# imu_cpu.net
KiCad netlist of a schematic drawn in Altium Designer
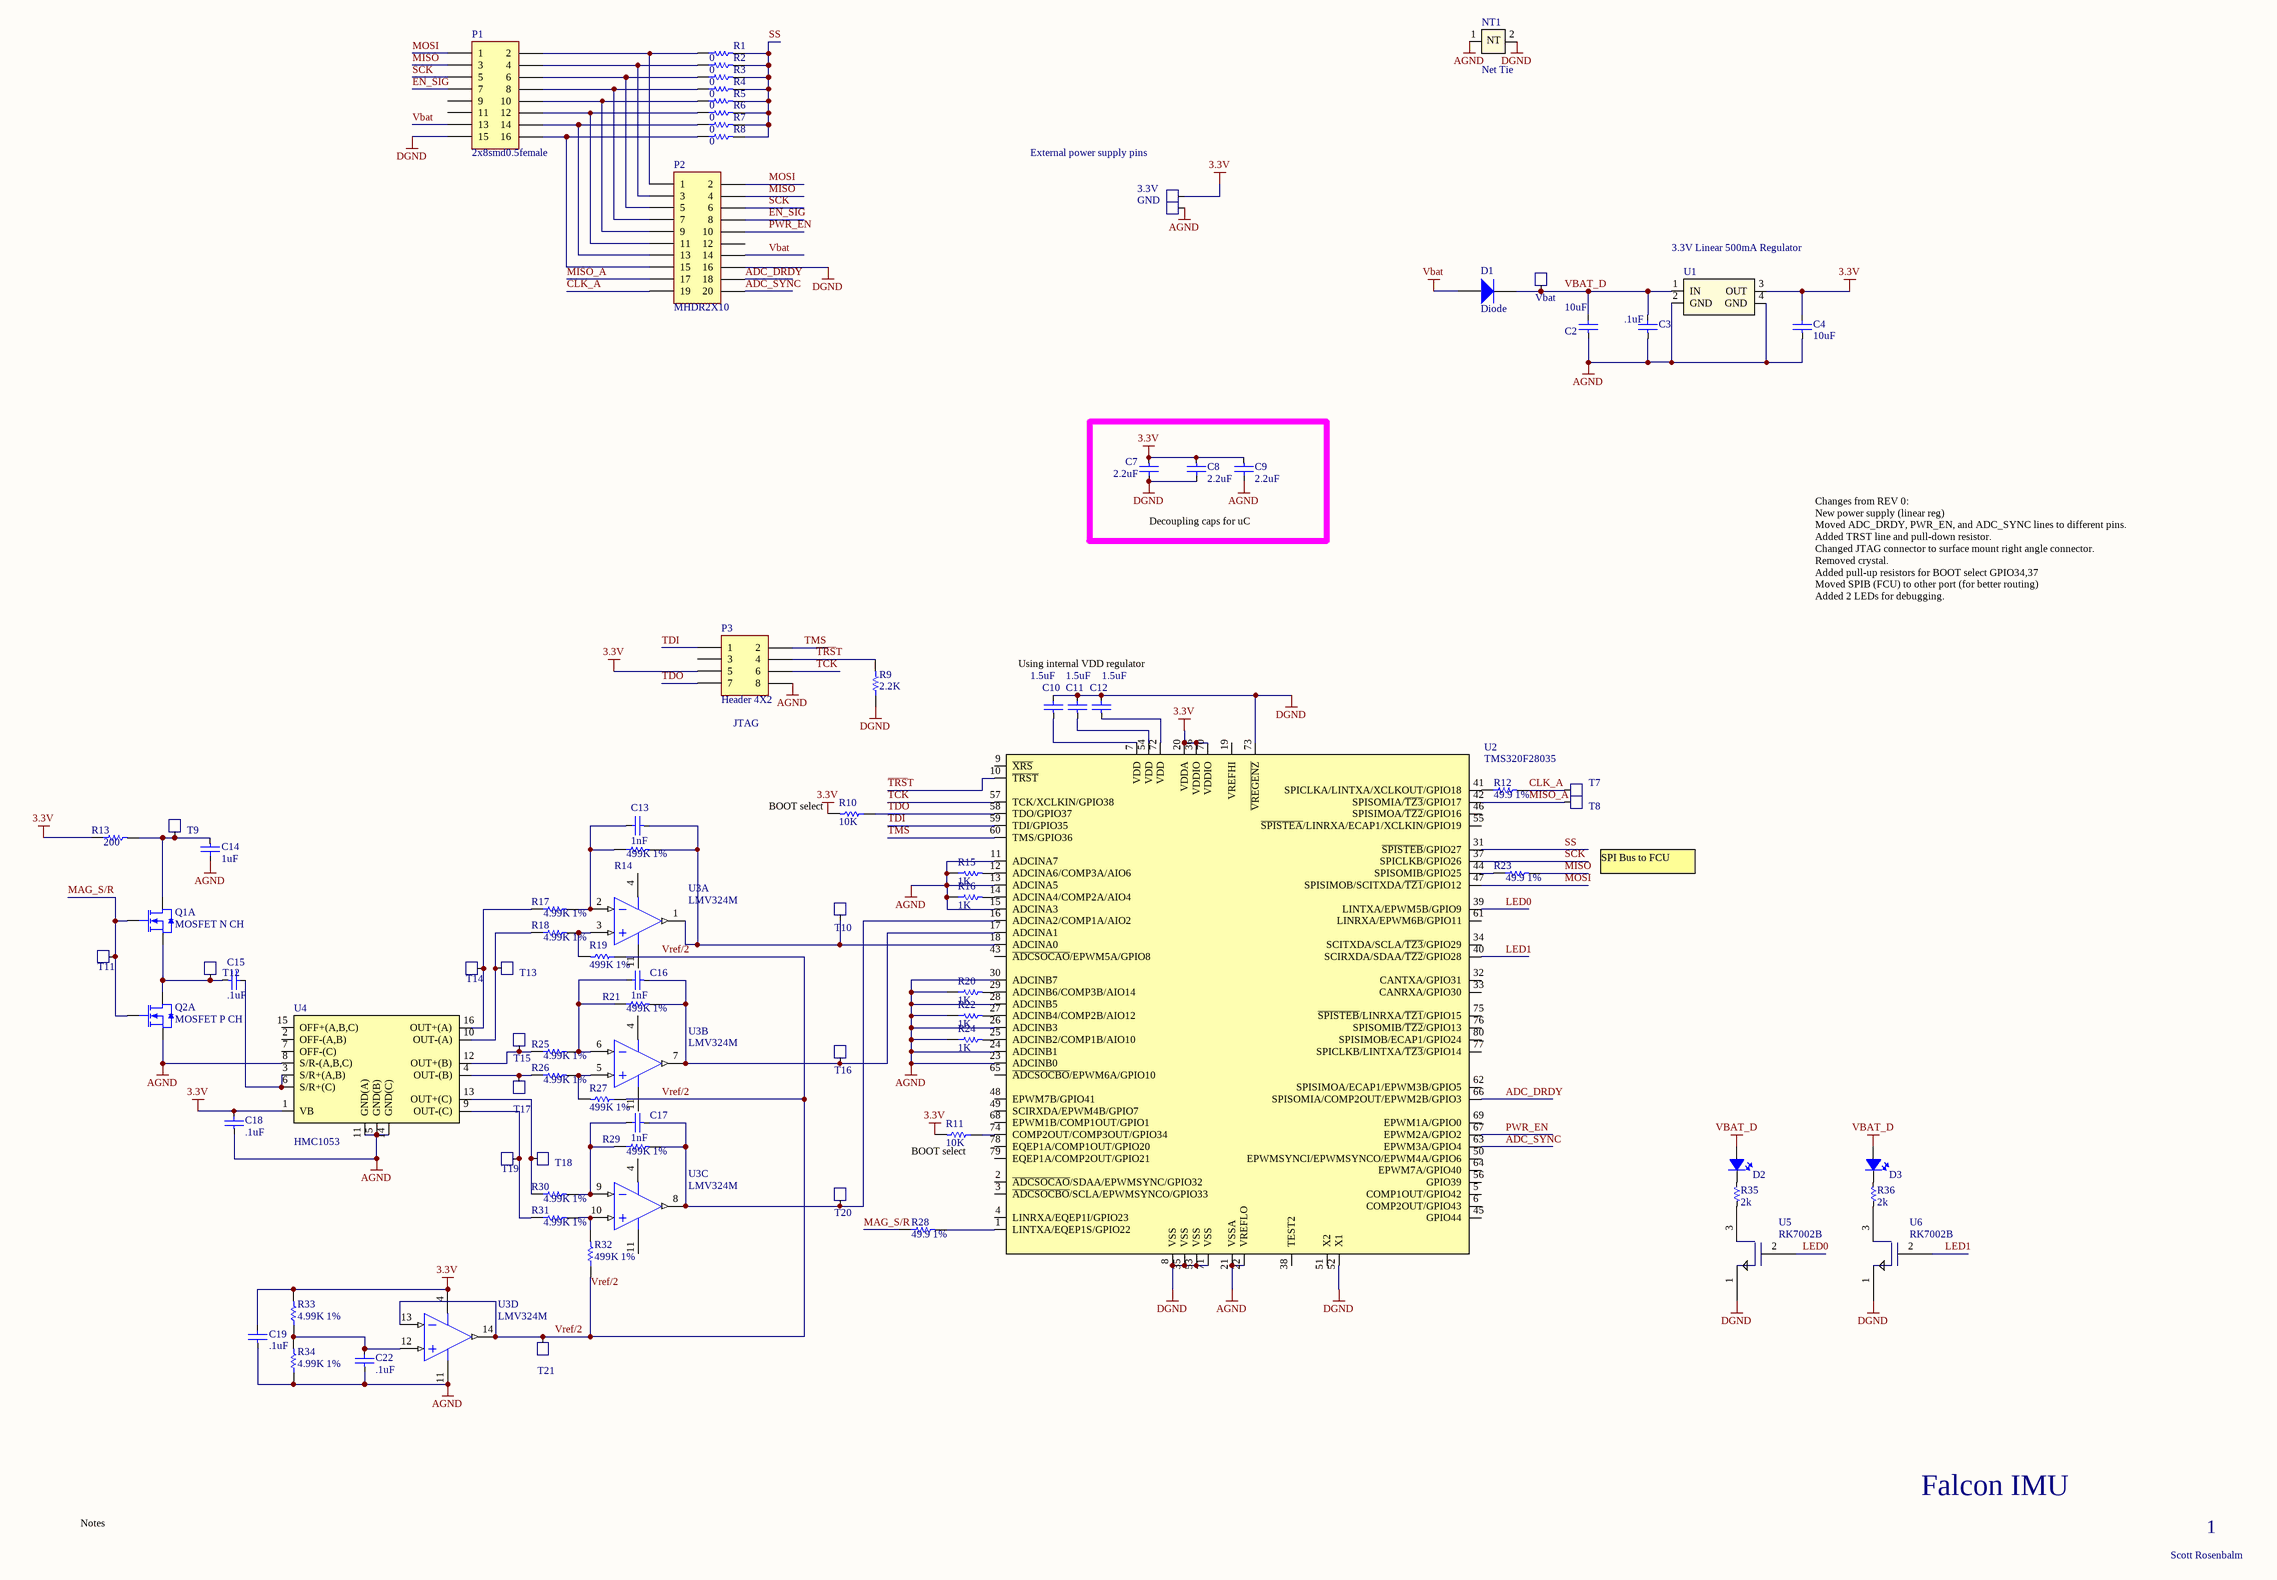
[diagram p0: imu_cpu.SchDoc]

(export (version "E")
  (design (tool "Eeschema 10.0.6"))
  (components
    (comp (ref "3.3V") (value "TEST_PAD") (footprint "TEST_PAD") (libsource (lib "") (part "TEST_PAD_1")))
    (comp (ref "C2")
      (value "10uF")
      (footprint "1210 (3225)")
      (fields (field (name "PART NO.") "810-C3225X7R1E106M"))
      (libsource (lib "SMT Chip") (part "Capacitor"))
    )
    (comp (ref "C3")
      (value ".1uF")
      (footprint "0603 (1608)")
      (fields (field (name "MANUFACTURER") "Murata") (field (name "PART NO.") "490-1524-1-ND"))
      (libsource (lib "SMT Chip") (part "Capacitor"))
    )
    (comp (ref "C4")
      (value "10uF")
      (footprint "1206 (3216)")
      (fields (field (name "PART NO.") "810-C3216X5R1A106M"))
      (libsource (lib "SMT Chip") (part "Capacitor"))
    )
    (comp (ref "C7")
      (value "2.2uF")
      (footprint "0603 (1608)")
      (fields
        (field (name "MANUFACTURER") "TDK")
        (field (name "PART NO.") "445-5167-1-ND")
        (field (name "TOLERANCE") "20%")
      )
      (libsource (lib "SMT Chip") (part "Capacitor"))
    )
    (comp (ref "C8")
      (value "2.2uF")
      (footprint "0603 (1608)")
      (fields
        (field (name "MANUFACTURER") "TDK")
        (field (name "PART NO.") "445-5167-1-ND")
        (field (name "TOLERANCE") "20%")
      )
      (libsource (lib "SMT Chip") (part "Capacitor"))
    )
    (comp (ref "C9")
      (value "2.2uF")
      (footprint "0603 (1608)")
      (fields
        (field (name "MANUFACTURER") "TDK")
        (field (name "PART NO.") "445-5167-1-ND")
        (field (name "TOLERANCE") "20%")
      )
      (libsource (lib "SMT Chip") (part "Capacitor"))
    )
    (comp (ref "C10")
      (value "1.5uF")
      (footprint "0805 (2012)")
      (fields (field (name "MANUFACTURER") "Murata") (field (name "PART NO.") "490-1740-1-ND"))
      (libsource (lib "SMT Chip") (part "Capacitor"))
    )
    (comp (ref "C11")
      (value "1.5uF")
      (footprint "0805 (2012)")
      (fields (field (name "MANUFACTURER") "Murata") (field (name "PART NO.") "490-1740-1-ND"))
      (libsource (lib "SMT Chip") (part "Capacitor"))
    )
    (comp (ref "C12")
      (value "1.5uF")
      (footprint "0805 (2012)")
      (fields (field (name "MANUFACTURER") "Murata") (field (name "PART NO.") "490-1740-1-ND"))
      (libsource (lib "SMT Chip") (part "Capacitor"))
    )
    (comp (ref "C13")
      (value "1nF")
      (footprint "0603 (1608)")
      (fields
        (field (name "MANUFACTURER") "Murata")
        (field (name "PART NO.") "490-1451-1-ND")
        (field (name "TOLERANCE") "5%")
      )
      (libsource (lib "SMT Chip") (part "Capacitor"))
    )
    (comp (ref "C14")
      (value "1uF")
      (footprint "0603 (1608)")
      (fields
        (field (name "MANUFACTURER") "Murata")
        (field (name "PART NO.") "81-GRM188R61E105KA12")
        (field (name "TOLERANCE") "10%")
      )
      (libsource (lib "SMT Chip") (part "Capacitor"))
    )
    (comp (ref "C15")
      (value ".1uF")
      (footprint "0603 (1608)")
      (fields
        (field (name "MANUFACTURER") "Murata")
        (field (name "PART NO.") "490-1524-1-ND")
        (field (name "Comment") "Capacitor")
      )
      (libsource (lib "SMT Chip") (part "Capacitor"))
    )
    (comp (ref "C16")
      (value "1nF")
      (footprint "0603 (1608)")
      (fields
        (field (name "MANUFACTURER") "Murata")
        (field (name "PART NO.") "490-1451-1-ND")
        (field (name "TOLERANCE") "5%")
      )
      (libsource (lib "SMT Chip") (part "Capacitor"))
    )
    (comp (ref "C17")
      (value "1nF")
      (footprint "0603 (1608)")
      (fields
        (field (name "MANUFACTURER") "Murata")
        (field (name "PART NO.") "490-1451-1-ND")
        (field (name "TOLERANCE") "5%")
      )
      (libsource (lib "SMT Chip") (part "Capacitor"))
    )
    (comp (ref "C18")
      (value ".1uF")
      (footprint "0603 (1608)")
      (fields
        (field (name "MANUFACTURER") "Murata")
        (field (name "PART NO.") "490-1524-1-ND")
        (field (name "Comment") "Capacitor")
      )
      (libsource (lib "SMT Chip") (part "Capacitor"))
    )
    (comp (ref "C19")
      (value ".1uF")
      (footprint "0603 (1608)")
      (fields
        (field (name "MANUFACTURER") "Murata")
        (field (name "PART NO.") "490-1524-1-ND")
        (field (name "Comment") "Capacitor")
      )
      (libsource (lib "SMT Chip") (part "Capacitor"))
    )
    (comp (ref "C22")
      (value ".1uF")
      (footprint "0603 (1608)")
      (fields
        (field (name "MANUFACTURER") "Murata")
        (field (name "PART NO.") "490-1524-1-ND")
        (field (name "Comment") "Capacitor")
      )
      (libsource (lib "SMT Chip") (part "Capacitor"))
    )
    (comp (ref "D1")
      (value "Diode")
      (footprint "0603(1608) diode - line on pin2")
      (description "Reverse voltage protection diode")
      (fields (field (name "PART NO.") "641-1332-1-ND"))
      (libsource (lib "Miscellaneous Devices") (part "Diode"))
    )
    (comp (ref "D2")
      (value "LED")
      (footprint "LED 0603 (1608)")
      (fields (field (name "PART NO.") "LTST-C170XXX") (field (name "MANUFACTURER") "Lite-On"))
      (libsource (lib "Diode") (part "LED"))
    )
    (comp (ref "D3")
      (value "LED")
      (footprint "LED 0603 (1608)")
      (fields (field (name "PART NO.") "LTST-C170XXX") (field (name "MANUFACTURER") "Lite-On"))
      (libsource (lib "Diode") (part "LED"))
    )
    (comp (ref "GND") (value "TEST_PAD") (footprint "TEST_PAD") (libsource (lib "") (part "TEST_PAD_1")))
    (comp (ref "NT1") (value "Net Tie") (footprint "NET_TIE") (libsource (lib "imu") (part "NET_TIE")))
    (comp (ref "P1")
      (value "2x8smd0.5female")
      (footprint "Header, right hole")
      (fields (field (name "PART NO.") "S9007E-08-ND"))
      (libsource (lib "imu") (part "2x8smd0.5female"))
    )
    (comp (ref "P2")
      (value "MHDR2X10")
      (footprint "S9013E-10-ND")
      (description "Header, 10-Pin, Dual row, Male")
      (fields (field (name "PART NO.") "S9013E-10-ND"))
      (libsource (lib "Miscellaneous Connectors") (part "MHDR2X10"))
    )
    (comp (ref "P3")
      (value "Header 4X2")
      (footprint "right-angle female header 8-pin")
      (description "Header, 4-Pin, Dual row")
      (fields (field (name "PART NO.") "3M9279CT-ND"))
      (libsource (lib "Miscellaneous Connectors") (part "Header 4X2"))
    )
    (comp (ref "Q1")
      (value "MOSFET N CH")
      (footprint "SOT563F")
      (fields (field (name "PART NO.") "SI1035X-T1-E3CT-ND") (field (name "MANUFACTURER") "Vishay Siliconx"))
      (libsource (lib "imu") (part "MOSFETs"))
    )
    (comp (ref "Q2")
      (value "MOSFET P CH")
      (footprint "SOT563F")
      (fields (field (name "PART NO.") "SI1035X-T1-E3CT-ND") (field (name "MANUFACTURER") "Vishay Siliconx"))
      (libsource (lib "imu") (part "MOSFETs"))
    )
    (comp (ref "R1")
      (value "0")
      (footprint "0603 (1608)")
      (description "Resistor")
      (fields (field (name "PART NO.") "P0.0GCT-ND") (field (name "Comment") "SS Jumper"))
      (libsource (lib "Miscellaneous Devices") (part "Res1"))
    )
    (comp (ref "R2")
      (value "0")
      (footprint "0603 (1608)")
      (description "Resistor")
      (fields (field (name "PART NO.") "P0.0GCT-ND") (field (name "Comment") "SS Jumper"))
      (libsource (lib "Miscellaneous Devices") (part "Res1"))
    )
    (comp (ref "R3")
      (value "0")
      (footprint "0603 (1608)")
      (description "Resistor")
      (fields (field (name "PART NO.") "P0.0GCT-ND") (field (name "Comment") "SS Jumper"))
      (libsource (lib "Miscellaneous Devices") (part "Res1"))
    )
    (comp (ref "R4")
      (value "0")
      (footprint "0603 (1608)")
      (description "Resistor")
      (fields (field (name "PART NO.") "P0.0GCT-ND") (field (name "Comment") "SS Jumper"))
      (libsource (lib "Miscellaneous Devices") (part "Res1"))
    )
    (comp (ref "R5")
      (value "0")
      (footprint "0603 (1608)")
      (description "Resistor")
      (fields (field (name "PART NO.") "P0.0GCT-ND") (field (name "Comment") "SS Jumper"))
      (libsource (lib "Miscellaneous Devices") (part "Res1"))
    )
    (comp (ref "R6")
      (value "0")
      (footprint "0603 (1608)")
      (description "Resistor")
      (fields (field (name "PART NO.") "P0.0GCT-ND") (field (name "Comment") "SS Jumper"))
      (libsource (lib "Miscellaneous Devices") (part "Res1"))
    )
    (comp (ref "R7")
      (value "0")
      (footprint "0603 (1608)")
      (description "Resistor")
      (fields (field (name "PART NO.") "P0.0GCT-ND") (field (name "Comment") "SS Jumper"))
      (libsource (lib "Miscellaneous Devices") (part "Res1"))
    )
    (comp (ref "R8")
      (value "0")
      (footprint "0603 (1608)")
      (description "Resistor")
      (fields (field (name "PART NO.") "P0.0GCT-ND") (field (name "Comment") "SS Jumper"))
      (libsource (lib "Miscellaneous Devices") (part "Res1"))
    )
    (comp (ref "R9")
      (value "2.2K")
      (footprint "0603 (1608)")
      (description "Resistor")
      (fields (field (name "PART NO.") "P2.2KGCT-ND") (field (name "Comment") "Res1"))
      (libsource (lib "Miscellaneous Devices") (part "Res1"))
    )
    (comp (ref "R10")
      (value "10K")
      (footprint "0603 (1608)")
      (description "Resistor")
      (fields (field (name "PART NO.") "541-10KGCT-ND") (field (name "Comment") "Res1"))
      (libsource (lib "Miscellaneous Devices") (part "Res1"))
    )
    (comp (ref "R11")
      (value "10K")
      (footprint "0603 (1608)")
      (description "Resistor")
      (fields (field (name "PART NO.") "541-10KGCT-ND") (field (name "Comment") "Res1"))
      (libsource (lib "Miscellaneous Devices") (part "Res1"))
    )
    (comp (ref "R12")
      (value "49.9 1%")
      (footprint "0603 (1608)")
      (description "Resistor")
      (fields (field (name "PART NO.") "P49.9HCT-ND") (field (name "Comment") "931 1%"))
      (libsource (lib "Miscellaneous Devices") (part "Res1"))
    )
    (comp (ref "R13")
      (value "200")
      (footprint "0603 (1608)")
      (description "Resistor")
      (fields (field (name "PART NO.") "P200GCT-ND"))
      (libsource (lib "Miscellaneous Devices") (part "Res1"))
    )
    (comp (ref "R14")
      (value "499K 1%")
      (footprint "0603 (1608)")
      (description "Resistor")
      (fields (field (name "PART NO.") "P499KHCT-ND"))
      (libsource (lib "Miscellaneous Devices") (part "Res1"))
    )
    (comp (ref "R15")
      (value "1K")
      (footprint "0603 (1608)")
      (description "Resistor")
      (fields (field (name "PART NO.") "P1.0KGCT-ND") (field (name "TOLERANCE") "5%"))
      (libsource (lib "Miscellaneous Devices") (part "Res1"))
    )
    (comp (ref "R16")
      (value "1K")
      (footprint "0603 (1608)")
      (description "Resistor")
      (fields (field (name "PART NO.") "P1.0KGCT-ND") (field (name "TOLERANCE") "5%"))
      (libsource (lib "Miscellaneous Devices") (part "Res1"))
    )
    (comp (ref "R17")
      (value "4.99K 1%")
      (footprint "0603 (1608)")
      (description "Resistor")
      (fields (field (name "PART NO.") "P4.99KHCT-ND") (field (name "Comment") "Res1"))
      (libsource (lib "Miscellaneous Devices") (part "Res1"))
    )
    (comp (ref "R18")
      (value "4.99K 1%")
      (footprint "0603 (1608)")
      (description "Resistor")
      (fields (field (name "PART NO.") "P4.99KHCT-ND") (field (name "Comment") "Res1"))
      (libsource (lib "Miscellaneous Devices") (part "Res1"))
    )
    (comp (ref "R19")
      (value "499K 1%")
      (footprint "0603 (1608)")
      (description "Resistor")
      (fields (field (name "PART NO.") "P499KHCT-ND"))
      (libsource (lib "Miscellaneous Devices") (part "Res1"))
    )
    (comp (ref "R20")
      (value "1K")
      (footprint "0603 (1608)")
      (description "Resistor")
      (fields (field (name "PART NO.") "P1.0KGCT-ND") (field (name "TOLERANCE") "5%"))
      (libsource (lib "Miscellaneous Devices") (part "Res1"))
    )
    (comp (ref "R21")
      (value "499K 1%")
      (footprint "0603 (1608)")
      (description "Resistor")
      (fields (field (name "PART NO.") "P499KHCT-ND"))
      (libsource (lib "Miscellaneous Devices") (part "Res1"))
    )
    (comp (ref "R22")
      (value "1K")
      (footprint "0603 (1608)")
      (description "Resistor")
      (fields (field (name "PART NO.") "P1.0KGCT-ND") (field (name "TOLERANCE") "5%"))
      (libsource (lib "Miscellaneous Devices") (part "Res1"))
    )
    (comp (ref "R23")
      (value "49.9 1%")
      (footprint "0603 (1608)")
      (description "Resistor")
      (fields (field (name "PART NO.") "P49.9HCT-ND") (field (name "Comment") "931 1%"))
      (libsource (lib "Miscellaneous Devices") (part "Res1"))
    )
    (comp (ref "R24")
      (value "1K")
      (footprint "0603 (1608)")
      (description "Resistor")
      (fields (field (name "PART NO.") "P1.0KGCT-ND") (field (name "TOLERANCE") "5%"))
      (libsource (lib "Miscellaneous Devices") (part "Res1"))
    )
    (comp (ref "R25")
      (value "4.99K 1%")
      (footprint "0603 (1608)")
      (description "Resistor")
      (fields (field (name "PART NO.") "P4.99KHCT-ND") (field (name "Comment") "Res1"))
      (libsource (lib "Miscellaneous Devices") (part "Res1"))
    )
    (comp (ref "R26")
      (value "4.99K 1%")
      (footprint "0603 (1608)")
      (description "Resistor")
      (fields (field (name "PART NO.") "P4.99KHCT-ND") (field (name "Comment") "Res1"))
      (libsource (lib "Miscellaneous Devices") (part "Res1"))
    )
    (comp (ref "R27")
      (value "499K 1%")
      (footprint "0603 (1608)")
      (description "Resistor")
      (fields (field (name "PART NO.") "P499KHCT-ND"))
      (libsource (lib "Miscellaneous Devices") (part "Res1"))
    )
    (comp (ref "R28")
      (value "49.9 1%")
      (footprint "0603 (1608)")
      (description "Resistor")
      (fields (field (name "PART NO.") "P49.9HCT-ND") (field (name "Comment") "931 1%"))
      (libsource (lib "Miscellaneous Devices") (part "Res1"))
    )
    (comp (ref "R29")
      (value "499K 1%")
      (footprint "0603 (1608)")
      (description "Resistor")
      (fields (field (name "PART NO.") "P499KHCT-ND"))
      (libsource (lib "Miscellaneous Devices") (part "Res1"))
    )
    (comp (ref "R30")
      (value "4.99K 1%")
      (footprint "0603 (1608)")
      (description "Resistor")
      (fields (field (name "PART NO.") "P4.99KHCT-ND") (field (name "Comment") "Res1"))
      (libsource (lib "Miscellaneous Devices") (part "Res1"))
    )
    (comp (ref "R31")
      (value "4.99K 1%")
      (footprint "0603 (1608)")
      (description "Resistor")
      (fields (field (name "PART NO.") "P4.99KHCT-ND") (field (name "Comment") "Res1"))
      (libsource (lib "Miscellaneous Devices") (part "Res1"))
    )
    (comp (ref "R32")
      (value "499K 1%")
      (footprint "0603 (1608)")
      (description "Resistor")
      (fields (field (name "PART NO.") "P499KHCT-ND"))
      (libsource (lib "Miscellaneous Devices") (part "Res1"))
    )
    (comp (ref "R33")
      (value "4.99K 1%")
      (footprint "0603 (1608)")
      (description "Resistor")
      (fields (field (name "PART NO.") "P4.99KHCT-ND") (field (name "Comment") "Res1"))
      (libsource (lib "Miscellaneous Devices") (part "Res1"))
    )
    (comp (ref "R34")
      (value "4.99K 1%")
      (footprint "0603 (1608)")
      (description "Resistor")
      (fields (field (name "PART NO.") "P4.99KHCT-ND") (field (name "Comment") "Res1"))
      (libsource (lib "Miscellaneous Devices") (part "Res1"))
    )
    (comp (ref "R35")
      (value "2k")
      (footprint "0603 (1608) BRACKET")
      (description "Resistor")
      (fields
        (field (name "PART NO.") "CRCW06031K00xxxxxxxxxx")
        (field (name "MANUFACTURER") "Vishay / Dale")
      )
      (libsource (lib "SMT Chip") (part "Resistor"))
    )
    (comp (ref "R36")
      (value "2k")
      (footprint "0603 (1608) BRACKET")
      (description "Resistor")
      (fields
        (field (name "PART NO.") "CRCW06031K00xxxxxxxxxx")
        (field (name "MANUFACTURER") "Vishay / Dale")
      )
      (libsource (lib "SMT Chip") (part "Resistor"))
    )
    (comp (ref "T7") (value "~") (footprint "TEST_PAD") (libsource (lib "") (part "TEST_PAD_3")))
    (comp (ref "T8") (value "~") (footprint "TEST_PAD") (libsource (lib "") (part "TEST_PAD_3")))
    (comp (ref "T9") (value "~") (footprint "TEST_PAD") (libsource (lib "imu") (part "TEST_PAD")))
    (comp (ref "T10") (value "~") (footprint "TEST_PAD") (libsource (lib "imu") (part "TEST_PAD")))
    (comp (ref "T11") (value "~") (footprint "TEST_PAD") (libsource (lib "") (part "TEST_PAD_1")))
    (comp (ref "T12") (value "~") (footprint "TEST_PAD") (libsource (lib "imu") (part "TEST_PAD")))
    (comp (ref "T13") (value "~") (footprint "TEST_PAD") (libsource (lib "") (part "TEST_PAD_3")))
    (comp (ref "T14") (value "~") (footprint "TEST_PAD") (libsource (lib "") (part "TEST_PAD_1")))
    (comp (ref "T15") (value "~") (footprint "TEST_PAD") (libsource (lib "imu") (part "TEST_PAD")))
    (comp (ref "T16") (value "~") (footprint "TEST_PAD") (libsource (lib "imu") (part "TEST_PAD")))
    (comp (ref "T17") (value "~") (footprint "TEST_PAD") (libsource (lib "") (part "TEST_PAD_2")))
    (comp (ref "T18") (value "~") (footprint "TEST_PAD") (libsource (lib "") (part "TEST_PAD_3")))
    (comp (ref "T19") (value "~") (footprint "TEST_PAD") (libsource (lib "") (part "TEST_PAD_1")))
    (comp (ref "T20") (value "~") (footprint "TEST_PAD") (libsource (lib "imu") (part "TEST_PAD")))
    (comp (ref "T21") (value "~") (footprint "TEST_PAD") (libsource (lib "") (part "TEST_PAD_2")))
    (comp (ref "U1")
      (value "3.3V Linear 500mA Regulator")
      (footprint "SOT233 (Ti voltage reg)")
      (fields (field (name "PART NO.") "296-13424-1-ND"))
      (libsource (lib "imu") (part "3.3V Linear 500mA Regulator"))
    )
    (comp (ref "U2")
      (value "TMS320F28035")
      (footprint "TS-PQFP-G80")
      (description "80-pin")
      (fields
        (field (name "MANUFACTURER") "Texas Instruments")
        (field (name "PART NO.") "TMS320F28035PNS-ND")
      )
      (libsource (lib "imu") (part "TMS320F28035 (80-pin)"))
    )
    (comp (ref "U3")
      (value "LMV324M")
      (footprint "M14A_N")
      (description "General Purpose, Low Voltage, Rail-to-Rail Output Operational Amplifiers")
      (fields
        (field (name "MANUFACTURER") "National Semiconductor")
        (field (name "PART NO.") "LMV324MXCT-ND")
        (field (name "DIGIKEYPARTNUMBER") "LMV324MXCT-ND")
        (field (name "PUBLISHER") "Altium Limited")
      )
      (libsource (lib "NSC Amplifier") (part "LMV324M"))
    )
    (comp (ref "U4")
      (value "HMC1053")
      (footprint "LCC-16")
      (fields (field (name "PART NO.") "342-1035-5-ND"))
      (libsource (lib "imu") (part "HMC1053"))
    )
    (comp (ref "U5") (value "RK7002B") (footprint "SOT-23-RK7002B") (libsource (lib "fcu") (part "RK7002B")))
    (comp (ref "U6") (value "RK7002B") (footprint "SOT-23-RK7002B") (libsource (lib "fcu") (part "RK7002B")))
    (comp (ref "Vbat") (value "TEST_PAD") (footprint "TEST_PAD") (libsource (lib "imu") (part "TEST_PAD")))
  )
  (nets
    (net (code "1") (name "/ADC_DRDY") (class "Default")
      (node (ref "P2") (pin "18") (pinfunction "18_18") (pintype "passive"))
      (node (ref "U2") (pin "66") (pinfunction "SPISOMIA/COMP2OUT/EPWM2B/GPIO3_66") (pintype "passive"))
    )
    (net (code "2") (name "/ADC_SYNC") (class "Default")
      (node (ref "P2") (pin "20") (pinfunction "20_20") (pintype "passive"))
      (node (ref "U2") (pin "63") (pinfunction "EPWM3A/GPIO4_63") (pintype "passive"))
    )
    (net (code "3") (name "/CLK_A") (class "Default")
      (node (ref "P2") (pin "19") (pinfunction "19_19") (pintype "passive"))
      (node (ref "R12") (pin "2") (pinfunction "2_2") (pintype "passive"))
      (node (ref "T7") (pin "0") (pintype "passive"))
    )
    (net (code "4") (name "/EN_SIG") (class "Default")
      (node (ref "P1") (pin "7") (pinfunction "7_7") (pintype "passive"))
      (node (ref "P2") (pin "8") (pinfunction "8_8") (pintype "passive"))
    )
    (net (code "5") (name "/LED0") (class "Default")
      (node (ref "U2") (pin "39") (pinfunction "LINTXA/EPWM5B/GPIO9_39") (pintype "passive"))
      (node (ref "U5") (pin "2") (pinfunction "G_2") (pintype "passive"))
    )
    (net (code "6") (name "/LED1") (class "Default")
      (node (ref "U2") (pin "40") (pinfunction "SCIRXDA/SDAA/~{TZ2}/GPIO28_40") (pintype "passive"))
      (node (ref "U6") (pin "2") (pinfunction "G_2") (pintype "passive"))
    )
    (net (code "7") (name "/MAG_S{slash}R") (class "Default")
      (node (ref "Q1") (pin "2") (pinfunction "G1_2") (pintype "passive"))
      (node (ref "Q2") (pin "2") (pinfunction "G1_2") (pintype "passive"))
      (node (ref "R28") (pin "1") (pinfunction "1_1") (pintype "passive"))
      (node (ref "T11") (pin "0") (pintype "passive"))
    )
    (net (code "8") (name "/MISO") (class "Default")
      (node (ref "P1") (pin "3") (pinfunction "3_3") (pintype "passive"))
      (node (ref "P2") (pin "4") (pinfunction "4_4") (pintype "passive"))
      (node (ref "R23") (pin "2") (pinfunction "2_2") (pintype "passive"))
    )
    (net (code "9") (name "/MISO_A") (class "Default")
      (node (ref "P2") (pin "17") (pinfunction "17_17") (pintype "passive"))
      (node (ref "T8") (pin "0") (pintype "passive"))
      (node (ref "U2") (pin "42") (pinfunction "SPISOMIA/~{TZ3}/GPIO17_42") (pintype "passive"))
    )
    (net (code "10") (name "/MOSI") (class "Default")
      (node (ref "P1") (pin "1") (pinfunction "1_1") (pintype "passive"))
      (node (ref "P2") (pin "2") (pinfunction "2_2") (pintype "passive"))
      (node (ref "U2") (pin "47") (pinfunction "SPISIMOB/SCITXDA/~{TZ1}/GPIO12_47") (pintype "passive"))
    )
    (net (code "11") (name "/PWR_EN") (class "Default")
      (node (ref "P2") (pin "10") (pinfunction "10_10") (pintype "passive"))
      (node (ref "U2") (pin "67") (pinfunction "EPWM2A/GPIO2_67") (pintype "passive"))
    )
    (net (code "12") (name "/SCK") (class "Default")
      (node (ref "P1") (pin "5") (pinfunction "5_5") (pintype "passive"))
      (node (ref "P2") (pin "6") (pinfunction "6_6") (pintype "passive"))
      (node (ref "U2") (pin "37") (pinfunction "SPICLKB/GPIO26_37") (pintype "passive"))
    )
    (net (code "13") (name "/SS") (class "Default")
      (node (ref "R1") (pin "2") (pinfunction "2_2") (pintype "passive"))
      (node (ref "R2") (pin "2") (pinfunction "2_2") (pintype "passive"))
      (node (ref "R3") (pin "2") (pinfunction "2_2") (pintype "passive"))
      (node (ref "R4") (pin "2") (pinfunction "2_2") (pintype "passive"))
      (node (ref "R5") (pin "2") (pinfunction "2_2") (pintype "passive"))
      (node (ref "R6") (pin "2") (pinfunction "2_2") (pintype "passive"))
      (node (ref "R7") (pin "2") (pinfunction "2_2") (pintype "passive"))
      (node (ref "R8") (pin "2") (pinfunction "2_2") (pintype "passive"))
      (node (ref "U2") (pin "31") (pinfunction "~{SPISTEB}/GPIO27_31") (pintype "passive"))
    )
    (net (code "14") (name "/TCK") (class "Default")
      (node (ref "P3") (pin "6") (pinfunction "6_6") (pintype "passive"))
      (node (ref "U2") (pin "57") (pinfunction "TCK/XCLKIN/GPIO38_57") (pintype "passive"))
    )
    (net (code "15") (name "/TDI") (class "Default")
      (node (ref "P3") (pin "1") (pinfunction "1_1") (pintype "passive"))
      (node (ref "U2") (pin "59") (pinfunction "TDI/GPIO35_59") (pintype "passive"))
    )
    (net (code "16") (name "/TDO") (class "Default")
      (node (ref "P3") (pin "7") (pinfunction "7_7") (pintype "passive"))
      (node (ref "R10") (pin "1") (pinfunction "1_1") (pintype "passive"))
      (node (ref "U2") (pin "58") (pinfunction "TDO/GPIO37_58") (pintype "passive"))
    )
    (net (code "17") (name "/TMS") (class "Default")
      (node (ref "P3") (pin "2") (pinfunction "2_2") (pintype "passive"))
      (node (ref "U2") (pin "60") (pinfunction "TMS/GPIO36_60") (pintype "passive"))
    )
    (net (code "18") (name "/Vref{slash}2") (class "Default")
      (node (ref "R19") (pin "1") (pinfunction "1_1") (pintype "passive"))
      (node (ref "R27") (pin "1") (pinfunction "1_1") (pintype "passive"))
      (node (ref "R32") (pin "1") (pinfunction "1_1") (pintype "passive"))
      (node (ref "T21") (pin "0") (pintype "passive"))
      (node (ref "U3") (pin "13") (pinfunction "IND-_13") (pintype "input"))
      (node (ref "U3") (pin "14") (pinfunction "OUTD_14") (pintype "output"))
    )
    (net (code "19") (name "/~{TRS}T") (class "Default")
      (node (ref "P3") (pin "4") (pinfunction "4_4") (pintype "passive"))
      (node (ref "R9") (pin "2") (pinfunction "2_2") (pintype "passive"))
      (node (ref "U2") (pin "10") (pinfunction "~{TRST}_10") (pintype "passive"))
    )
    (net (code "20") (name "3.3V") (class "Default")
      (node (ref "3.3V") (pin "0") (pintype "passive"))
      (node (ref "C18") (pin "1") (pinfunction "1_1") (pintype "passive"))
      (node (ref "C19") (pin "1") (pinfunction "1_1") (pintype "passive"))
      (node (ref "C4") (pin "1") (pinfunction "1_1") (pintype "passive"))
      (node (ref "C7") (pin "2") (pinfunction "2_2") (pintype "passive"))
      (node (ref "C8") (pin "2") (pinfunction "2_2") (pintype "passive"))
      (node (ref "C9") (pin "2") (pinfunction "2_2") (pintype "passive"))
      (node (ref "P3") (pin "5") (pinfunction "5_5") (pintype "passive"))
      (node (ref "R10") (pin "2") (pinfunction "2_2") (pintype "passive"))
      (node (ref "R11") (pin "2") (pinfunction "2_2") (pintype "passive"))
      (node (ref "R13") (pin "1") (pinfunction "1_1") (pintype "passive"))
      (node (ref "R33") (pin "2") (pinfunction "2_2") (pintype "passive"))
      (node (ref "U1") (pin "3") (pinfunction "OUT_3") (pintype "passive"))
      (node (ref "U2") (pin "20") (pinfunction "VDDA_20") (pintype "passive"))
      (node (ref "U2") (pin "36") (pinfunction "VDDIO_36") (pintype "passive"))
      (node (ref "U2") (pin "70") (pinfunction "VDDIO_70") (pintype "passive"))
      (node (ref "U3") (pin "4") (pinfunction "V+_4") (pintype "power_in"))
      (node (ref "U4") (pin "1") (pinfunction "VB_1") (pintype "passive"))
    )
    (net (code "21") (name "AGND") (class "Default")
      (node (ref "C14") (pin "1") (pinfunction "1_1") (pintype "passive"))
      (node (ref "C18") (pin "2") (pinfunction "2_2") (pintype "passive"))
      (node (ref "C19") (pin "2") (pinfunction "2_2") (pintype "passive"))
      (node (ref "C2") (pin "2") (pinfunction "2_2") (pintype "passive"))
      (node (ref "C22") (pin "2") (pinfunction "2_2") (pintype "passive"))
      (node (ref "C3") (pin "2") (pinfunction "2_2") (pintype "passive"))
      (node (ref "C4") (pin "2") (pinfunction "2_2") (pintype "passive"))
      (node (ref "C9") (pin "1") (pinfunction "1_1") (pintype "passive"))
      (node (ref "GND") (pin "0") (pintype "passive"))
      (node (ref "NT1") (pin "1") (pintype "passive"))
      (node (ref "P3") (pin "8") (pinfunction "8_8") (pintype "passive"))
      (node (ref "Q2") (pin "1") (pinfunction "S1_1") (pintype "passive"))
      (node (ref "R15") (pin "1") (pinfunction "1_1") (pintype "passive"))
      (node (ref "R16") (pin "1") (pinfunction "1_1") (pintype "passive"))
      (node (ref "R20") (pin "1") (pinfunction "1_1") (pintype "passive"))
      (node (ref "R22") (pin "1") (pinfunction "1_1") (pintype "passive"))
      (node (ref "R24") (pin "1") (pinfunction "1_1") (pintype "passive"))
      (node (ref "R34") (pin "1") (pinfunction "1_1") (pintype "passive"))
      (node (ref "U1") (pin "2") (pinfunction "GND_2") (pintype "passive"))
      (node (ref "U1") (pin "4") (pinfunction "GND_4") (pintype "passive"))
      (node (ref "U2") (pin "11") (pinfunction "ADCINA7_11") (pintype "passive"))
      (node (ref "U2") (pin "13") (pinfunction "ADCINA5_13") (pintype "passive"))
      (node (ref "U2") (pin "15") (pinfunction "ADCINA3_15") (pintype "passive"))
      (node (ref "U2") (pin "21") (pinfunction "VSSA_21") (pintype "passive"))
      (node (ref "U2") (pin "22") (pinfunction "VREFLO_22") (pintype "passive"))
      (node (ref "U2") (pin "23") (pinfunction "ADCINB0_23") (pintype "passive"))
      (node (ref "U2") (pin "24") (pinfunction "ADCINB1_24") (pintype "passive"))
      (node (ref "U2") (pin "26") (pinfunction "ADCINB3_26") (pintype "passive"))
      (node (ref "U2") (pin "28") (pinfunction "ADCINB5_28") (pintype "passive"))
      (node (ref "U2") (pin "30") (pinfunction "ADCINB7_30") (pintype "passive"))
      (node (ref "U3") (pin "11") (pinfunction "V-_11") (pintype "power_in"))
      (node (ref "U4") (pin "11") (pinfunction "GND(A)_11") (pintype "passive"))
      (node (ref "U4") (pin "14") (pinfunction "GND(C)_14") (pintype "passive"))
      (node (ref "U4") (pin "5") (pinfunction "GND(B)_5") (pintype "passive"))
      (node (ref "U4") (pin "8") (pinfunction "S/R-(A,B,C)_8") (pintype "passive"))
    )
    (net (code "22") (name "DGND") (class "Default")
      (node (ref "C10") (pin "1") (pinfunction "1_1") (pintype "passive"))
      (node (ref "C11") (pin "1") (pinfunction "1_1") (pintype "passive"))
      (node (ref "C12") (pin "1") (pinfunction "1_1") (pintype "passive"))
      (node (ref "C7") (pin "1") (pinfunction "1_1") (pintype "passive"))
      (node (ref "C8") (pin "1") (pinfunction "1_1") (pintype "passive"))
      (node (ref "NT1") (pin "2") (pintype "passive"))
      (node (ref "P1") (pin "15") (pinfunction "15_15") (pintype "passive"))
      (node (ref "P2") (pin "16") (pinfunction "16_16") (pintype "passive"))
      (node (ref "R9") (pin "1") (pinfunction "1_1") (pintype "passive"))
      (node (ref "U2") (pin "35") (pinfunction "VSS_35") (pintype "passive"))
      (node (ref "U2") (pin "52") (pinfunction "X1_52") (pintype "passive"))
      (node (ref "U2") (pin "53") (pinfunction "VSS_53") (pintype "passive"))
      (node (ref "U2") (pin "71") (pinfunction "VSS_71") (pintype "passive"))
      (node (ref "U2") (pin "73") (pinfunction "~{VREGENZ}_73") (pintype "passive"))
      (node (ref "U2") (pin "8") (pinfunction "VSS_8") (pintype "passive"))
      (node (ref "U5") (pin "1") (pinfunction "S_1") (pintype "passive"))
      (node (ref "U6") (pin "1") (pinfunction "S_1") (pintype "passive"))
    )
    (net (code "23") (name "Net-(C10-Pad2)") (class "Default")
      (node (ref "C10") (pin "2") (pinfunction "2_2") (pintype "passive"))
      (node (ref "U2") (pin "7") (pinfunction "VDD_7") (pintype "passive"))
    )
    (net (code "24") (name "Net-(C11-Pad2)") (class "Default")
      (node (ref "C11") (pin "2") (pinfunction "2_2") (pintype "passive"))
      (node (ref "U2") (pin "54") (pinfunction "VDD_54") (pintype "passive"))
    )
    (net (code "25") (name "Net-(C12-Pad2)") (class "Default")
      (node (ref "C12") (pin "2") (pinfunction "2_2") (pintype "passive"))
      (node (ref "U2") (pin "72") (pinfunction "VDD_72") (pintype "passive"))
    )
    (net (code "26") (name "Net-(D2-Pad2)") (class "Default")
      (node (ref "D2") (pin "2") (pinfunction "2_2") (pintype "passive"))
      (node (ref "R35") (pin "1") (pinfunction "1_1") (pintype "passive"))
    )
    (net (code "27") (name "Net-(D3-Pad2)") (class "Default")
      (node (ref "D3") (pin "2") (pinfunction "2_2") (pintype "passive"))
      (node (ref "R36") (pin "1") (pinfunction "1_1") (pintype "passive"))
    )
    (net (code "28") (name "Net-(P1-Pad2)") (class "Default")
      (node (ref "P1") (pin "2") (pinfunction "2_2") (pintype "passive"))
      (node (ref "P2") (pin "1") (pinfunction "1_1") (pintype "passive"))
      (node (ref "R1") (pin "1") (pinfunction "1_1") (pintype "passive"))
    )
    (net (code "29") (name "Net-(P1-Pad4)") (class "Default")
      (node (ref "P1") (pin "4") (pinfunction "4_4") (pintype "passive"))
      (node (ref "P2") (pin "3") (pinfunction "3_3") (pintype "passive"))
      (node (ref "R2") (pin "1") (pinfunction "1_1") (pintype "passive"))
    )
    (net (code "30") (name "Net-(P1-Pad6)") (class "Default")
      (node (ref "P1") (pin "6") (pinfunction "6_6") (pintype "passive"))
      (node (ref "P2") (pin "5") (pinfunction "5_5") (pintype "passive"))
      (node (ref "R3") (pin "1") (pinfunction "1_1") (pintype "passive"))
    )
    (net (code "31") (name "Net-(P1-Pad8)") (class "Default")
      (node (ref "P1") (pin "8") (pinfunction "8_8") (pintype "passive"))
      (node (ref "P2") (pin "7") (pinfunction "7_7") (pintype "passive"))
      (node (ref "R4") (pin "1") (pinfunction "1_1") (pintype "passive"))
    )
    (net (code "32") (name "Net-(P1-Pad10)") (class "Default")
      (node (ref "P1") (pin "10") (pinfunction "10_10") (pintype "passive"))
      (node (ref "P2") (pin "9") (pinfunction "9_9") (pintype "passive"))
      (node (ref "R5") (pin "1") (pinfunction "1_1") (pintype "passive"))
    )
    (net (code "33") (name "Net-(P1-Pad12)") (class "Default")
      (node (ref "P1") (pin "12") (pinfunction "12_12") (pintype "passive"))
      (node (ref "P2") (pin "11") (pinfunction "11_11") (pintype "passive"))
      (node (ref "R6") (pin "1") (pinfunction "1_1") (pintype "passive"))
    )
    (net (code "34") (name "Net-(P1-Pad14)") (class "Default")
      (node (ref "P1") (pin "14") (pinfunction "14_14") (pintype "passive"))
      (node (ref "P2") (pin "13") (pinfunction "13_13") (pintype "passive"))
      (node (ref "R7") (pin "1") (pinfunction "1_1") (pintype "passive"))
    )
    (net (code "35") (name "Net-(P1-Pad16)") (class "Default")
      (node (ref "P1") (pin "16") (pinfunction "16_16") (pintype "passive"))
      (node (ref "P2") (pin "15") (pinfunction "15_15") (pintype "passive"))
      (node (ref "R8") (pin "1") (pinfunction "1_1") (pintype "passive"))
    )
    (net (code "36") (name "Net-(Q1A-D1)") (class "Default")
      (node (ref "C14") (pin "2") (pinfunction "2_2") (pintype "passive"))
      (node (ref "Q1") (pin "6") (pinfunction "D1_6") (pintype "passive"))
      (node (ref "R13") (pin "2") (pinfunction "2_2") (pintype "passive"))
      (node (ref "T9") (pin "0") (pintype "passive"))
    )
    (net (code "37") (name "Net-(Q1A-S1)") (class "Default")
      (node (ref "C15") (pin "2") (pinfunction "2_2") (pintype "passive"))
      (node (ref "Q1") (pin "1") (pinfunction "S1_1") (pintype "passive"))
      (node (ref "Q2") (pin "6") (pinfunction "D1_6") (pintype "passive"))
      (node (ref "T12") (pin "0") (pintype "passive"))
    )
    (net (code "38") (name "Net-(U2-ADCINA0)") (class "Default")
      (node (ref "C13") (pin "2") (pinfunction "2_2") (pintype "passive"))
      (node (ref "R14") (pin "2") (pinfunction "2_2") (pintype "passive"))
      (node (ref "T10") (pin "0") (pintype "passive"))
      (node (ref "U2") (pin "18") (pinfunction "ADCINA0_18") (pintype "passive"))
      (node (ref "U3") (pin "1") (pinfunction "OUTA_1") (pintype "output"))
    )
    (net (code "39") (name "Net-(U2-ADCINA1)") (class "Default")
      (node (ref "C16") (pin "2") (pinfunction "2_2") (pintype "passive"))
      (node (ref "R21") (pin "2") (pinfunction "2_2") (pintype "passive"))
      (node (ref "T16") (pin "0") (pintype "passive"))
      (node (ref "U2") (pin "17") (pinfunction "ADCINA1_17") (pintype "passive"))
      (node (ref "U3") (pin "7") (pinfunction "OUTB_7") (pintype "output"))
    )
    (net (code "40") (name "Net-(U2-ADCINA2{slash}COMP1A{slash}AIO2)") (class "Default")
      (node (ref "C17") (pin "2") (pinfunction "2_2") (pintype "passive"))
      (node (ref "R29") (pin "2") (pinfunction "2_2") (pintype "passive"))
      (node (ref "T20") (pin "0") (pintype "passive"))
      (node (ref "U2") (pin "16") (pinfunction "ADCINA2/COMP1A/AIO2_16") (pintype "passive"))
      (node (ref "U3") (pin "8") (pinfunction "OUTC_8") (pintype "output"))
    )
    (net (code "41") (name "Net-(U2-ADCINA4{slash}COMP2A{slash}AIO4)") (class "Default")
      (node (ref "R16") (pin "2") (pinfunction "2_2") (pintype "passive"))
      (node (ref "U2") (pin "14") (pinfunction "ADCINA4/COMP2A/AIO4_14") (pintype "passive"))
    )
    (net (code "42") (name "Net-(U2-ADCINA6{slash}COMP3A{slash}AIO6)") (class "Default")
      (node (ref "R15") (pin "2") (pinfunction "2_2") (pintype "passive"))
      (node (ref "U2") (pin "12") (pinfunction "ADCINA6/COMP3A/AIO6_12") (pintype "passive"))
    )
    (net (code "43") (name "Net-(U2-ADCINB2{slash}COMP1B{slash}AIO10)") (class "Default")
      (node (ref "R24") (pin "2") (pinfunction "2_2") (pintype "passive"))
      (node (ref "U2") (pin "25") (pinfunction "ADCINB2/COMP1B/AIO10_25") (pintype "passive"))
    )
    (net (code "44") (name "Net-(U2-ADCINB4{slash}COMP2B{slash}AIO12)") (class "Default")
      (node (ref "R22") (pin "2") (pinfunction "2_2") (pintype "passive"))
      (node (ref "U2") (pin "27") (pinfunction "ADCINB4/COMP2B/AIO12_27") (pintype "passive"))
    )
    (net (code "45") (name "Net-(U2-ADCINB6{slash}COMP3B{slash}AIO14)") (class "Default")
      (node (ref "R20") (pin "2") (pinfunction "2_2") (pintype "passive"))
      (node (ref "U2") (pin "29") (pinfunction "ADCINB6/COMP3B/AIO14_29") (pintype "passive"))
    )
    (net (code "46") (name "Net-(U2-COMP2OUT{slash}COMP3OUT{slash}GPIO34)") (class "Default")
      (node (ref "R11") (pin "1") (pinfunction "1_1") (pintype "passive"))
      (node (ref "U2") (pin "74") (pinfunction "COMP2OUT/COMP3OUT/GPIO34_74") (pintype "passive"))
    )
    (net (code "47") (name "Net-(U2-LINTXA{slash}EQEP1S{slash}GPIO22)") (class "Default")
      (node (ref "R28") (pin "2") (pinfunction "2_2") (pintype "passive"))
      (node (ref "U2") (pin "1") (pinfunction "LINTXA/EQEP1S/GPIO22_1") (pintype "passive"))
    )
    (net (code "48") (name "Net-(U2-SPICLKA{slash}LINTXA{slash}XCLKOUT{slash}GPIO18)") (class "Default")
      (node (ref "R12") (pin "1") (pinfunction "1_1") (pintype "passive"))
      (node (ref "U2") (pin "41") (pinfunction "SPICLKA/LINTXA/XCLKOUT/GPIO18_41") (pintype "passive"))
    )
    (net (code "49") (name "Net-(U2-SPISOMIB{slash}GPIO25)") (class "Default")
      (node (ref "R23") (pin "1") (pinfunction "1_1") (pintype "passive"))
      (node (ref "U2") (pin "44") (pinfunction "SPISOMIB/GPIO25_44") (pintype "passive"))
    )
    (net (code "50") (name "Net-(U3A-INA+)") (class "Default")
      (node (ref "R18") (pin "2") (pinfunction "2_2") (pintype "passive"))
      (node (ref "R19") (pin "2") (pinfunction "2_2") (pintype "passive"))
      (node (ref "U3") (pin "3") (pinfunction "INA+_3") (pintype "input"))
    )
    (net (code "51") (name "Net-(U3A-INA-)") (class "Default")
      (node (ref "C13") (pin "1") (pinfunction "1_1") (pintype "passive"))
      (node (ref "R14") (pin "1") (pinfunction "1_1") (pintype "passive"))
      (node (ref "R17") (pin "2") (pinfunction "2_2") (pintype "passive"))
      (node (ref "U3") (pin "2") (pinfunction "INA-_2") (pintype "input"))
    )
    (net (code "52") (name "Net-(U3B-INB+)") (class "Default")
      (node (ref "R26") (pin "2") (pinfunction "2_2") (pintype "passive"))
      (node (ref "R27") (pin "2") (pinfunction "2_2") (pintype "passive"))
      (node (ref "U3") (pin "5") (pinfunction "INB+_5") (pintype "input"))
    )
    (net (code "53") (name "Net-(U3B-INB-)") (class "Default")
      (node (ref "C16") (pin "1") (pinfunction "1_1") (pintype "passive"))
      (node (ref "R21") (pin "1") (pinfunction "1_1") (pintype "passive"))
      (node (ref "R25") (pin "2") (pinfunction "2_2") (pintype "passive"))
      (node (ref "U3") (pin "6") (pinfunction "INB-_6") (pintype "input"))
    )
    (net (code "54") (name "Net-(U3C-INC+)") (class "Default")
      (node (ref "R31") (pin "2") (pinfunction "2_2") (pintype "passive"))
      (node (ref "R32") (pin "2") (pinfunction "2_2") (pintype "passive"))
      (node (ref "U3") (pin "10") (pinfunction "INC+_10") (pintype "input"))
    )
    (net (code "55") (name "Net-(U3C-INC-)") (class "Default")
      (node (ref "C17") (pin "1") (pinfunction "1_1") (pintype "passive"))
      (node (ref "R29") (pin "1") (pinfunction "1_1") (pintype "passive"))
      (node (ref "R30") (pin "2") (pinfunction "2_2") (pintype "passive"))
      (node (ref "U3") (pin "9") (pinfunction "INC-_9") (pintype "input"))
    )
    (net (code "56") (name "Net-(U3D-IND+)") (class "Default")
      (node (ref "C22") (pin "1") (pinfunction "1_1") (pintype "passive"))
      (node (ref "R33") (pin "1") (pinfunction "1_1") (pintype "passive"))
      (node (ref "R34") (pin "2") (pinfunction "2_2") (pintype "passive"))
      (node (ref "U3") (pin "12") (pinfunction "IND+_12") (pintype "input"))
    )
    (net (code "57") (name "Net-(U4-OUT+(A))") (class "Default")
      (node (ref "R17") (pin "1") (pinfunction "1_1") (pintype "passive"))
      (node (ref "T14") (pin "0") (pintype "passive"))
      (node (ref "U4") (pin "16") (pinfunction "OUT+(A)_16") (pintype "passive"))
    )
    (net (code "58") (name "Net-(U4-OUT+(B))") (class "Default")
      (node (ref "R25") (pin "1") (pinfunction "1_1") (pintype "passive"))
      (node (ref "T15") (pin "0") (pintype "passive"))
      (node (ref "U4") (pin "12") (pinfunction "OUT+(B)_12") (pintype "passive"))
    )
    (net (code "59") (name "Net-(U4-OUT+(C))") (class "Default")
      (node (ref "R30") (pin "1") (pinfunction "1_1") (pintype "passive"))
      (node (ref "T18") (pin "0") (pintype "passive"))
      (node (ref "U4") (pin "13") (pinfunction "OUT+(C)_13") (pintype "passive"))
    )
    (net (code "60") (name "Net-(U4-OUT-(A))") (class "Default")
      (node (ref "R18") (pin "1") (pinfunction "1_1") (pintype "passive"))
      (node (ref "T13") (pin "0") (pintype "passive"))
      (node (ref "U4") (pin "10") (pinfunction "OUT-(A)_10") (pintype "passive"))
    )
    (net (code "61") (name "Net-(U4-OUT-(B))") (class "Default")
      (node (ref "R26") (pin "1") (pinfunction "1_1") (pintype "passive"))
      (node (ref "T17") (pin "0") (pintype "passive"))
      (node (ref "U4") (pin "4") (pinfunction "OUT-(B)_4") (pintype "passive"))
    )
    (net (code "62") (name "Net-(U4-OUT-(C))") (class "Default")
      (node (ref "R31") (pin "1") (pinfunction "1_1") (pintype "passive"))
      (node (ref "T19") (pin "0") (pintype "passive"))
      (node (ref "U4") (pin "9") (pinfunction "OUT-(C)_9") (pintype "passive"))
    )
    (net (code "63") (name "Net-(U4-S{slash}R+(A,B))") (class "Default")
      (node (ref "C15") (pin "1") (pinfunction "1_1") (pintype "passive"))
      (node (ref "U4") (pin "3") (pinfunction "S/R+(A,B)_3") (pintype "passive"))
      (node (ref "U4") (pin "6") (pinfunction "S/R+(C)_6") (pintype "passive"))
    )
    (net (code "64") (name "Net-(U5-D)") (class "Default")
      (node (ref "R35") (pin "2") (pinfunction "2_2") (pintype "passive"))
      (node (ref "U5") (pin "3") (pinfunction "D_3") (pintype "passive"))
    )
    (net (code "65") (name "Net-(U6-D)") (class "Default")
      (node (ref "R36") (pin "2") (pinfunction "2_2") (pintype "passive"))
      (node (ref "U6") (pin "3") (pinfunction "D_3") (pintype "passive"))
    )
    (net (code "66") (name "VBAT_D") (class "Default")
      (node (ref "C2") (pin "1") (pinfunction "1_1") (pintype "passive"))
      (node (ref "C3") (pin "1") (pinfunction "1_1") (pintype "passive"))
      (node (ref "D1") (pin "2") (pinfunction "K_2") (pintype "passive"))
      (node (ref "D2") (pin "1") (pinfunction "1_1") (pintype "passive"))
      (node (ref "D3") (pin "1") (pinfunction "1_1") (pintype "passive"))
      (node (ref "U1") (pin "1") (pinfunction "IN_1") (pintype "passive"))
      (node (ref "Vbat") (pin "0") (pintype "passive"))
    )
    (net (code "67") (name "Vbat") (class "Default")
      (node (ref "D1") (pin "1") (pinfunction "A_1") (pintype "passive"))
      (node (ref "P1") (pin "13") (pinfunction "13_13") (pintype "passive"))
      (node (ref "P2") (pin "14") (pinfunction "14_14") (pintype "passive"))
    )
    (net (code "68") (name "unconnected-(P1-Pad9)") (class "Default")
      (node (ref "P1") (pin "9") (pinfunction "9_9") (pintype "passive"))
    )
    (net (code "69") (name "unconnected-(P1-Pad11)") (class "Default")
      (node (ref "P1") (pin "11") (pinfunction "11_11") (pintype "passive"))
    )
    (net (code "70") (name "unconnected-(P2-Pad12)") (class "Default")
      (node (ref "P2") (pin "12") (pinfunction "12_12") (pintype "passive"))
    )
    (net (code "71") (name "unconnected-(P3-Pad3)") (class "Default")
      (node (ref "P3") (pin "3") (pinfunction "3_3") (pintype "passive"))
    )
    (net (code "72") (name "unconnected-(U2-CANRXA{slash}GPIO30-Pad33)") (class "Default")
      (node (ref "U2") (pin "33") (pinfunction "CANRXA/GPIO30_33") (pintype "passive"))
    )
    (net (code "73") (name "unconnected-(U2-CANTXA{slash}GPIO31-Pad32)") (class "Default")
      (node (ref "U2") (pin "32") (pinfunction "CANTXA/GPIO31_32") (pintype "passive"))
    )
    (net (code "74") (name "unconnected-(U2-COMP1OUT{slash}GPIO42-Pad5)") (class "Default")
      (node (ref "U2") (pin "5") (pinfunction "COMP1OUT/GPIO42_5") (pintype "passive"))
    )
    (net (code "75") (name "unconnected-(U2-COMP2OUT{slash}GPIO43-Pad6)") (class "Default")
      (node (ref "U2") (pin "6") (pinfunction "COMP2OUT/GPIO43_6") (pintype "passive"))
    )
    (net (code "76") (name "unconnected-(U2-EPWM1A{slash}GPIO0-Pad69)") (class "Default")
      (node (ref "U2") (pin "69") (pinfunction "EPWM1A/GPIO0_69") (pintype "passive"))
    )
    (net (code "77") (name "unconnected-(U2-EPWM1B{slash}COMP1OUT{slash}GPIO1-Pad68)") (class "Default")
      (node (ref "U2") (pin "68") (pinfunction "EPWM1B/COMP1OUT/GPIO1_68") (pintype "passive"))
    )
    (net (code "78") (name "unconnected-(U2-EPWM7A{slash}GPIO40-Pad64)") (class "Default")
      (node (ref "U2") (pin "64") (pinfunction "EPWM7A/GPIO40_64") (pintype "passive"))
    )
    (net (code "79") (name "unconnected-(U2-EPWM7B{slash}GPIO41-Pad48)") (class "Default")
      (node (ref "U2") (pin "48") (pinfunction "EPWM7B/GPIO41_48") (pintype "passive"))
    )
    (net (code "80") (name "unconnected-(U2-EPWMSYNCI{slash}EPWMSYNCO{slash}EPWM4A{slash}GPIO6-Pad50)") (class "Default")
      (node (ref "U2") (pin "50") (pinfunction "EPWMSYNCI/EPWMSYNCO/EPWM4A/GPIO6_50") (pintype "passive"))
    )
    (net (code "81") (name "unconnected-(U2-EQEP1A{slash}COMP1OUT{slash}GPIO20-Pad78)") (class "Default")
      (node (ref "U2") (pin "78") (pinfunction "EQEP1A/COMP1OUT/GPIO20_78") (pintype "passive"))
    )
    (net (code "82") (name "unconnected-(U2-EQEP1A{slash}COMP2OUT{slash}GPIO21-Pad79)") (class "Default")
      (node (ref "U2") (pin "79") (pinfunction "EQEP1A/COMP2OUT/GPIO21_79") (pintype "passive"))
    )
    (net (code "83") (name "unconnected-(U2-GPIO39-Pad56)") (class "Default")
      (node (ref "U2") (pin "56") (pinfunction "GPIO39_56") (pintype "passive"))
    )
    (net (code "84") (name "unconnected-(U2-GPIO44-Pad45)") (class "Default")
      (node (ref "U2") (pin "45") (pinfunction "GPIO44_45") (pintype "passive"))
    )
    (net (code "85") (name "unconnected-(U2-LINRXA{slash}EPWM6B{slash}GPIO11-Pad61)") (class "Default")
      (node (ref "U2") (pin "61") (pinfunction "LINRXA/EPWM6B/GPIO11_61") (pintype "passive"))
    )
    (net (code "86") (name "unconnected-(U2-LINRXA{slash}EQEP1I{slash}GPIO23-Pad4)") (class "Default")
      (node (ref "U2") (pin "4") (pinfunction "LINRXA/EQEP1I/GPIO23_4") (pintype "passive"))
    )
    (net (code "87") (name "unconnected-(U2-SCIRXDA{slash}EPWM4B{slash}GPIO7-Pad49)") (class "Default")
      (node (ref "U2") (pin "49") (pinfunction "SCIRXDA/EPWM4B/GPIO7_49") (pintype "passive"))
    )
    (net (code "88") (name "unconnected-(U2-SCITXDA{slash}SCLA{slash}~{TZ3}{slash}GPIO29-Pad34)") (class "Default")
      (node (ref "U2") (pin "34") (pinfunction "SCITXDA/SCLA/~{TZ3}/GPIO29_34") (pintype "passive"))
    )
    (net (code "89") (name "unconnected-(U2-SPICLKB{slash}LINTXA{slash}~{TZ3}{slash}GPIO14-Pad77)") (class "Default")
      (node (ref "U2") (pin "77") (pinfunction "SPICLKB/LINTXA/~{TZ3}/GPIO14_77") (pintype "passive"))
    )
    (net (code "90") (name "unconnected-(U2-SPISIMOA{slash}ECAP1{slash}EPWM3B{slash}GPIO5-Pad62)") (class "Default")
      (node (ref "U2") (pin "62") (pinfunction "SPISIMOA/ECAP1/EPWM3B/GPIO5_62") (pintype "passive"))
    )
    (net (code "91") (name "unconnected-(U2-SPISIMOA{slash}~{TZ2}{slash}GPIO16-Pad46)") (class "Default")
      (node (ref "U2") (pin "46") (pinfunction "SPISIMOA/~{TZ2}/GPIO16_46") (pintype "passive"))
    )
    (net (code "92") (name "unconnected-(U2-SPISIMOB{slash}ECAP1{slash}GPIO24-Pad80)") (class "Default")
      (node (ref "U2") (pin "80") (pinfunction "SPISIMOB/ECAP1/GPIO24_80") (pintype "passive"))
    )
    (net (code "93") (name "unconnected-(U2-SPISOMIB{slash}~{TZ2}{slash}GPIO13-Pad76)") (class "Default")
      (node (ref "U2") (pin "76") (pinfunction "SPISOMIB/~{TZ2}/GPIO13_76") (pintype "passive"))
    )
    (net (code "94") (name "unconnected-(U2-TEST2-Pad38)") (class "Default")
      (node (ref "U2") (pin "38") (pinfunction "TEST2_38") (pintype "passive"))
    )
    (net (code "95") (name "unconnected-(U2-VREFHI-Pad19)") (class "Default")
      (node (ref "U2") (pin "19") (pinfunction "VREFHI_19") (pintype "passive"))
    )
    (net (code "96") (name "unconnected-(U2-X2-Pad51)") (class "Default")
      (node (ref "U2") (pin "51") (pinfunction "X2_51") (pintype "passive"))
    )
    (net (code "97") (name "unconnected-(U2-~{ADCSOCAO}{slash}EPWM5A{slash}GPIO8-Pad43)") (class "Default")
      (node (ref "U2") (pin "43") (pinfunction "~{ADCSOCAO}/EPWM5A/GPIO8_43") (pintype "passive"))
    )
    (net (code "98") (name "unconnected-(U2-~{ADCSOCAO}{slash}SDAA{slash}EPWMSYNC{slash}GPIO32-Pad2)") (class "Default")
      (node (ref "U2") (pin "2") (pinfunction "~{ADCSOCAO}/SDAA/EPWMSYNC/GPIO32_2") (pintype "passive"))
    )
    (net (code "99") (name "unconnected-(U2-~{ADCSOCBO}{slash}EPWM6A{slash}GPIO10-Pad65)") (class "Default")
      (node (ref "U2") (pin "65") (pinfunction "~{ADCSOCBO}/EPWM6A/GPIO10_65") (pintype "passive"))
    )
    (net (code "100") (name "unconnected-(U2-~{ADCSOCBO}{slash}SCLA{slash}EPWMSYNCO{slash}GPIO33-Pad3)") (class "Default")
      (node (ref "U2") (pin "3") (pinfunction "~{ADCSOCBO}/SCLA/EPWMSYNCO/GPIO33_3") (pintype "passive"))
    )
    (net (code "101") (name "unconnected-(U2-~{SPISTEA}{slash}LINRXA{slash}ECAP1{slash}XCLKIN{slash}GPIO19-Pad55)") (class "Default")
      (node (ref "U2") (pin "55") (pinfunction "~{SPISTEA}/LINRXA/ECAP1/XCLKIN/GPIO19_55") (pintype "passive"))
    )
    (net (code "102") (name "unconnected-(U2-~{SPISTEB}{slash}LINRXA{slash}~{TZ1}{slash}GPIO15-Pad75)") (class "Default")
      (node (ref "U2") (pin "75") (pinfunction "~{SPISTEB}/LINRXA/~{TZ1}/GPIO15_75") (pintype "passive"))
    )
    (net (code "103") (name "unconnected-(U2-~{XRS}-Pad9)") (class "Default")
      (node (ref "U2") (pin "9") (pinfunction "~{XRS}_9") (pintype "passive"))
    )
    (net (code "104") (name "unconnected-(U3A-V+-Pad4)") (class "Default")
      (node (ref "U3") (pin "4") (pinfunction "V+_4") (pintype "power_in"))
    )
    (net (code "105") (name "unconnected-(U3A-V--Pad11)") (class "Default")
      (node (ref "U3") (pin "11") (pinfunction "V-_11") (pintype "power_in"))
    )
    (net (code "106") (name "unconnected-(U3B-V+-Pad4)") (class "Default")
      (node (ref "U3") (pin "4") (pinfunction "V+_4") (pintype "power_in"))
    )
    (net (code "107") (name "unconnected-(U3B-V--Pad11)") (class "Default")
      (node (ref "U3") (pin "11") (pinfunction "V-_11") (pintype "power_in"))
    )
    (net (code "108") (name "unconnected-(U3C-V+-Pad4)") (class "Default")
      (node (ref "U3") (pin "4") (pinfunction "V+_4") (pintype "power_in"))
    )
    (net (code "109") (name "unconnected-(U3C-V--Pad11)") (class "Default")
      (node (ref "U3") (pin "11") (pinfunction "V-_11") (pintype "power_in"))
    )
    (net (code "110") (name "unconnected-(U4-OFF+(A,B,C)-Pad15)") (class "Default")
      (node (ref "U4") (pin "15") (pinfunction "OFF+(A,B,C)_15") (pintype "passive"))
    )
    (net (code "111") (name "unconnected-(U4-OFF-(A,B)-Pad2)") (class "Default")
      (node (ref "U4") (pin "2") (pinfunction "OFF-(A,B)_2") (pintype "passive"))
    )
    (net (code "112") (name "unconnected-(U4-OFF-(C)-Pad7)") (class "Default")
      (node (ref "U4") (pin "7") (pinfunction "OFF-(C)_7") (pintype "passive"))
    )
  )
)
